# 03-POWER.net
KiCad netlist of a schematic drawn in Altium Designer
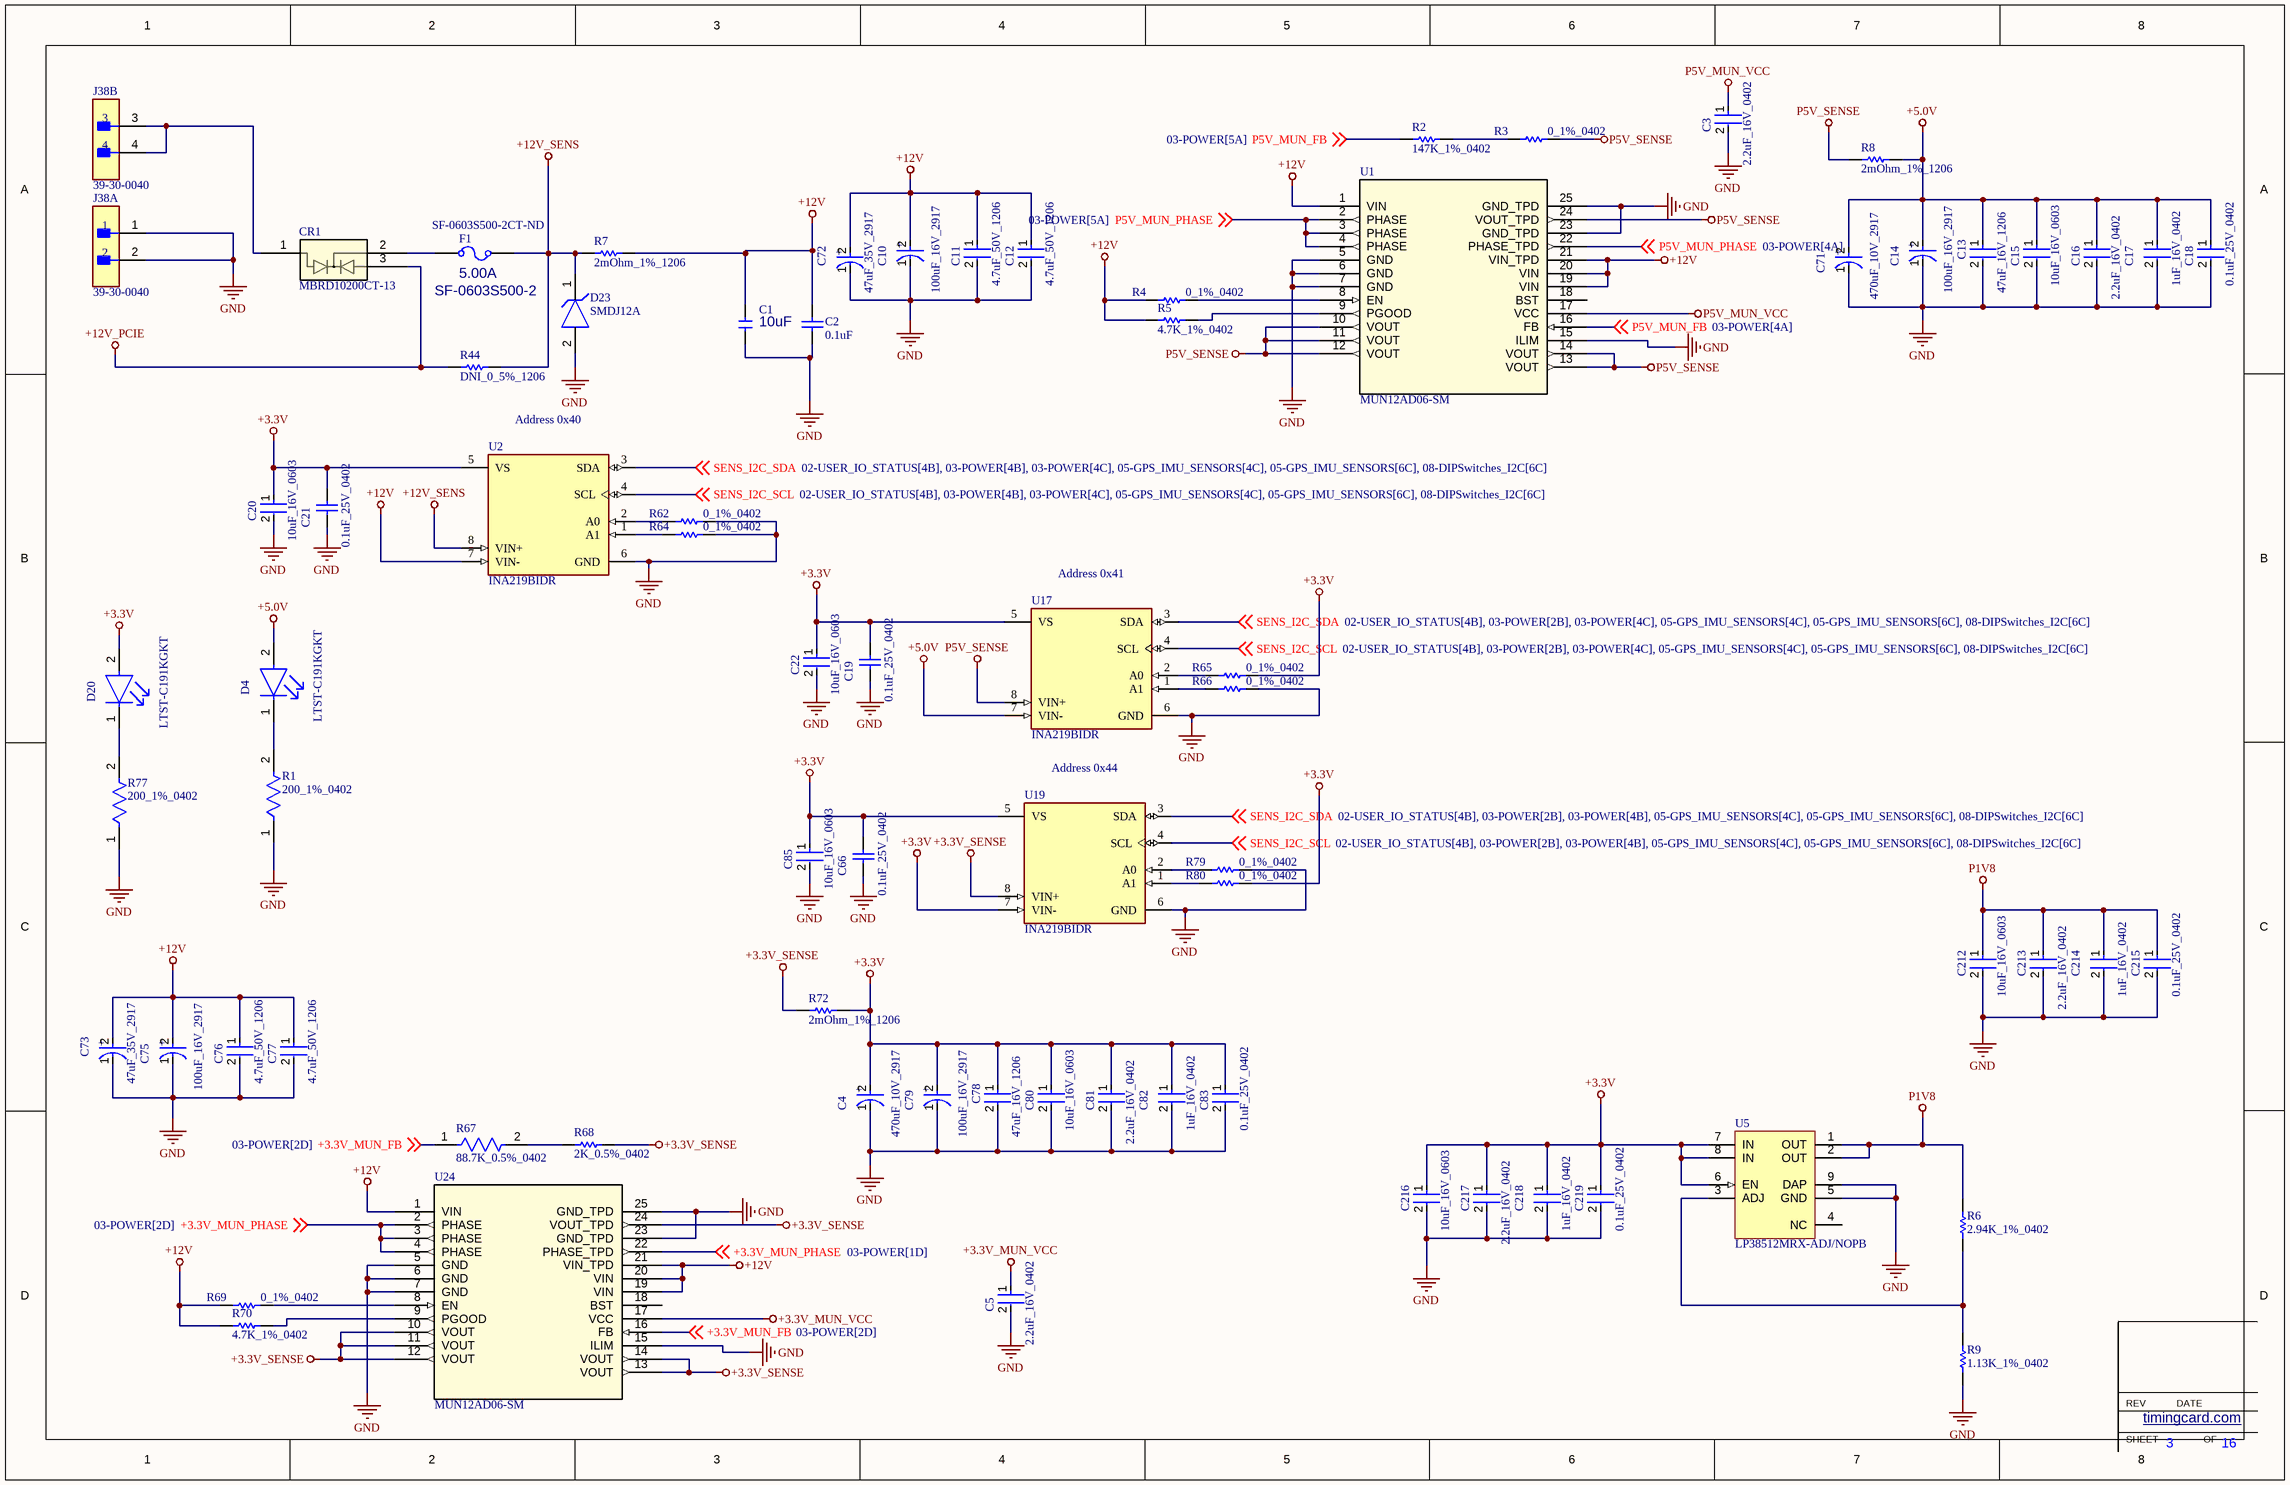
[diagram p0: 03-POWER.SchDoc]

(export (version "E")
  (design (tool "Eeschema 10.0.6"))
  (components
    (comp (ref "C1")
      (value "10uF")
      (footprint "CAPC2012X14N")
      (description "CAP, CER, 10.UF, 25V, 10%, X5R, 0805")
      (fields
        (field (name "MFG PART NUM") "TMK212BBJ106KG-T")
        (field (name "VALENTIUM PART NUM") "<VALENTIUM>")
      )
      (libsource (lib "Capacitors") (part "CAP_0805_10UF_25V"))
    )
    (comp (ref "C2")
      (value "0.1uF")
      (footprint "CAPC1608X87X45ML20T05")
      (description "C0603X104K5RACAUTO")
      (fields (field (name "MANUFACTURER") "Kemet"))
      (libsource (lib "Altium Content Vault") (part "CAP"))
    )
    (comp (ref "C3")
      (value "2.2uF_16V_0402")
      (footprint "FP-C1005-050-0_05-IPC_A")
      (description "Multilayer Ceramic Capacitors 2.2μF ±10% 16V X5R SMD 0402")
      (fields (field (name "TOLERANCE") "10%"))
      (libsource (lib "Altium Content Vault") (part "b4654b650e69147ec39a6b967a45e02"))
    )
    (comp (ref "C4")
      (value "470uF_10V_2917")
      (footprint "FP-TAJE-MFG")
      (description "470uF 10V  ±10% 500mΩ 2917  SMD Tantalum Capacitor")
      (fields (field (name "TOLERANCE") "10%") (field (name "VOLTAGE") "10V"))
      (libsource (lib "Altium Content Vault") (part "203bc49f2ac43e59fd269a8c329ed05"))
    )
    (comp (ref "C5")
      (value "2.2uF_16V_0402")
      (footprint "FP-C1005-050-0_05-IPC_A")
      (description "Multilayer Ceramic Capacitors 2.2μF ±10% 16V X5R SMD 0402")
      (fields (field (name "TOLERANCE") "10%"))
      (libsource (lib "Altium Content Vault") (part "b4654b650e69147ec39a6b967a45e02"))
    )
    (comp (ref "C10")
      (value "100uF_16V_2917")
      (footprint "FP-T495D107K016ATE125-MFG")
      (description "CAP TANT 100UF 10% 16V 2917")
      (fields (field (name "VOLTAGE") "16V") (field (name "TOLERANCE") "10%"))
      (libsource (lib "Altium Content Vault") (part "a00bbbee19879c290e62620ae7e47b1"))
    )
    (comp (ref "C11")
      (value "4.7uF_50V_1206")
      (footprint "FP-GRM31C-0_2-e0_3_0_8-IPC_C")
      (description "Chip Multilayer Ceramic Capacitors for General Purpose, 1206, 4.7uF, X7R, 15%, 10%, 50V")
      (fields (field (name "VOLTAGE") "50V") (field (name "TOLERANCE") "10%"))
      (libsource (lib "Altium Content Vault") (part "02cd4be3c70576c341d710602a673aa"))
    )
    (comp (ref "C12")
      (value "4.7uF_50V_1206")
      (footprint "FP-GRM31C-0_2-e0_3_0_8-IPC_C")
      (description "Chip Multilayer Ceramic Capacitors for General Purpose, 1206, 4.7uF, X7R, 15%, 10%, 50V")
      (fields (field (name "VOLTAGE") "50V") (field (name "TOLERANCE") "10%"))
      (libsource (lib "Altium Content Vault") (part "02cd4be3c70576c341d710602a673aa"))
    )
    (comp (ref "C13")
      (value "47uF_16V_1206")
      (footprint "FP-C3216-160-0_2-MFG")
      (description "Multilayer Ceramic Capacitors 47uF ±20% 16V X5R SMD 1206")
      (fields (field (name "TOLERANCE") "20%"))
      (libsource (lib "Altium Content Vault") (part "11868f565c42a9108669ba33697ecf6"))
    )
    (comp (ref "C14")
      (value "100uF_16V_2917")
      (footprint "FP-T495D107K016ATE125-MFG")
      (description "CAP TANT 100UF 10% 16V 2917")
      (fields (field (name "VOLTAGE") "16V") (field (name "TOLERANCE") "10%"))
      (libsource (lib "Altium Content Vault") (part "a00bbbee19879c290e62620ae7e47b1"))
    )
    (comp (ref "C15")
      (value "10uF_16V_0603")
      (footprint "FP-0603-L_1_6_0_2-W_0_8_0-MFG")
      (description "Multilayer Ceramic Capacitor 10uF 16V X5R 20% SMD 0603 T/R")
      (fields (field (name "TOLERANCE") "20%"))
      (libsource (lib "Altium Content Vault") (part "b4654b650e69147ec39a6b967a45e02"))
    )
    (comp (ref "C16")
      (value "2.2uF_16V_0402")
      (footprint "FP-C1005-050-0_05-IPC_A")
      (description "Multilayer Ceramic Capacitors 2.2μF ±10% 16V X5R SMD 0402")
      (fields (field (name "TOLERANCE") "10%"))
      (libsource (lib "Altium Content Vault") (part "b4654b650e69147ec39a6b967a45e02"))
    )
    (comp (ref "C17")
      (value "1uF_16V_0402")
      (footprint "FP-0402-L_1_0_0_05-W_0_5-IPC_A")
      (description "None")
      (fields (field (name "TOLERANCE") "10%"))
      (libsource (lib "Altium Content Vault") (part "b4654b650e69147ec39a6b967a45e02"))
    )
    (comp (ref "C18")
      (value "0.1uF_25V_0402")
      (footprint "FP-0402-L_1_0_1-W_0_5_0_1-IPC_C")
      (description "General Purpose Ceramic Capacitor, 0402, 100nF, 10%, X7R, 15%, 25V")
      (fields (field (name "VOLTAGE") "25V") (field (name "TOLERANCE") "10%"))
      (libsource (lib "Altium Content Vault") (part "b4654b650e69147ec39a6b967a45e02"))
    )
    (comp (ref "C19")
      (value "0.1uF_25V_0402")
      (footprint "CAPC1005X56X25NL10T15")
      (fields
        (field (name "PART NUMBER") "04023D104KAT2A")
        (field (name "MANUFACTURER") "AVX Interconnect / Elco")
      )
      (libsource (lib "Altium Content Vault") (part "CAP"))
    )
    (comp (ref "C20")
      (value "10uF_16V_0603")
      (footprint "FP-0603-L_1_6_0_2-W_0_8_0-MFG")
      (description "Multilayer Ceramic Capacitor 10uF 16V X5R 20% SMD 0603 T/R")
      (fields (field (name "TOLERANCE") "20%"))
      (libsource (lib "Altium Content Vault") (part "b4654b650e69147ec39a6b967a45e02"))
    )
    (comp (ref "C21")
      (value "0.1uF_25V_0402")
      (footprint "CAPC1005X56X25NL10T15")
      (fields
        (field (name "PART NUMBER") "04023D104KAT2A")
        (field (name "MANUFACTURER") "AVX Interconnect / Elco")
      )
      (libsource (lib "Altium Content Vault") (part "CAP"))
    )
    (comp (ref "C22")
      (value "10uF_16V_0603")
      (footprint "FP-0603-L_1_6_0_2-W_0_8_0-MFG")
      (description "Multilayer Ceramic Capacitor 10uF 16V X5R 20% SMD 0603 T/R")
      (fields (field (name "TOLERANCE") "20%"))
      (libsource (lib "Altium Content Vault") (part "b4654b650e69147ec39a6b967a45e02"))
    )
    (comp (ref "C66")
      (value "0.1uF_25V_0402")
      (footprint "CAPC1005X56X25NL10T15")
      (fields
        (field (name "PART NUMBER") "04023D104KAT2A")
        (field (name "MANUFACTURER") "AVX Interconnect / Elco")
      )
      (libsource (lib "Altium Content Vault") (part "CAP"))
    )
    (comp (ref "C71")
      (value "470uF_10V_2917")
      (footprint "FP-TAJE-MFG")
      (description "470uF 10V  ±10% 500mΩ 2917  SMD Tantalum Capacitor")
      (fields (field (name "TOLERANCE") "10%") (field (name "VOLTAGE") "10V"))
      (libsource (lib "Altium Content Vault") (part "203bc49f2ac43e59fd269a8c329ed05"))
    )
    (comp (ref "C72")
      (value "47uF_35V_2917")
      (footprint "FP-T521X476M035ATE030-MFG")
      (description "CAP TANT POLY 47UF 35V 2917")
      (fields (field (name "TOLERANCE") "20%"))
      (libsource (lib "Altium Content Vault") (part "a00bbbee19879c290e62620ae7e47b1"))
    )
    (comp (ref "C73")
      (value "47uF_35V_2917")
      (footprint "FP-T521X476M035ATE030-MFG")
      (description "CAP TANT POLY 47UF 35V 2917")
      (fields (field (name "TOLERANCE") "20%"))
      (libsource (lib "Altium Content Vault") (part "a00bbbee19879c290e62620ae7e47b1"))
    )
    (comp (ref "C75")
      (value "100uF_16V_2917")
      (footprint "FP-T495D107K016ATE125-MFG")
      (description "CAP TANT 100UF 10% 16V 2917")
      (fields (field (name "VOLTAGE") "16V") (field (name "TOLERANCE") "10%"))
      (libsource (lib "Altium Content Vault") (part "a00bbbee19879c290e62620ae7e47b1"))
    )
    (comp (ref "C76")
      (value "4.7uF_50V_1206")
      (footprint "FP-GRM31C-0_2-e0_3_0_8-IPC_C")
      (description "Chip Multilayer Ceramic Capacitors for General Purpose, 1206, 4.7uF, X7R, 15%, 10%, 50V")
      (fields (field (name "VOLTAGE") "50V") (field (name "TOLERANCE") "10%"))
      (libsource (lib "Altium Content Vault") (part "02cd4be3c70576c341d710602a673aa"))
    )
    (comp (ref "C77")
      (value "4.7uF_50V_1206")
      (footprint "FP-GRM31C-0_2-e0_3_0_8-IPC_C")
      (description "Chip Multilayer Ceramic Capacitors for General Purpose, 1206, 4.7uF, X7R, 15%, 10%, 50V")
      (fields (field (name "VOLTAGE") "50V") (field (name "TOLERANCE") "10%"))
      (libsource (lib "Altium Content Vault") (part "02cd4be3c70576c341d710602a673aa"))
    )
    (comp (ref "C78")
      (value "47uF_16V_1206")
      (footprint "FP-C3216-160-0_2-MFG")
      (description "Multilayer Ceramic Capacitors 47uF ±20% 16V X5R SMD 1206")
      (fields (field (name "TOLERANCE") "20%"))
      (libsource (lib "Altium Content Vault") (part "11868f565c42a9108669ba33697ecf6"))
    )
    (comp (ref "C79")
      (value "100uF_16V_2917")
      (footprint "FP-T495D107K016ATE125-MFG")
      (description "CAP TANT 100UF 10% 16V 2917")
      (fields (field (name "VOLTAGE") "16V") (field (name "TOLERANCE") "10%"))
      (libsource (lib "Altium Content Vault") (part "a00bbbee19879c290e62620ae7e47b1"))
    )
    (comp (ref "C80")
      (value "10uF_16V_0603")
      (footprint "FP-0603-L_1_6_0_2-W_0_8_0-MFG")
      (description "Multilayer Ceramic Capacitor 10uF 16V X5R 20% SMD 0603 T/R")
      (fields (field (name "TOLERANCE") "20%"))
      (libsource (lib "Altium Content Vault") (part "b4654b650e69147ec39a6b967a45e02"))
    )
    (comp (ref "C81")
      (value "2.2uF_16V_0402")
      (footprint "FP-C1005-050-0_05-IPC_A")
      (description "Multilayer Ceramic Capacitors 2.2μF ±10% 16V X5R SMD 0402")
      (fields (field (name "TOLERANCE") "10%"))
      (libsource (lib "Altium Content Vault") (part "b4654b650e69147ec39a6b967a45e02"))
    )
    (comp (ref "C82")
      (value "1uF_16V_0402")
      (footprint "FP-0402-L_1_0_0_05-W_0_5-IPC_A")
      (description "None")
      (fields (field (name "TOLERANCE") "10%"))
      (libsource (lib "Altium Content Vault") (part "b4654b650e69147ec39a6b967a45e02"))
    )
    (comp (ref "C83")
      (value "0.1uF_25V_0402")
      (footprint "FP-0402-L_1_0_1-W_0_5_0_1-IPC_C")
      (description "General Purpose Ceramic Capacitor, 0402, 100nF, 10%, X7R, 15%, 25V")
      (fields (field (name "VOLTAGE") "25V") (field (name "TOLERANCE") "10%"))
      (libsource (lib "Altium Content Vault") (part "b4654b650e69147ec39a6b967a45e02"))
    )
    (comp (ref "C85")
      (value "10uF_16V_0603")
      (footprint "FP-0603-L_1_6_0_2-W_0_8_0-MFG")
      (description "Multilayer Ceramic Capacitor 10uF 16V X5R 20% SMD 0603 T/R")
      (fields (field (name "TOLERANCE") "20%"))
      (libsource (lib "Altium Content Vault") (part "b4654b650e69147ec39a6b967a45e02"))
    )
    (comp (ref "C212")
      (value "10uF_16V_0603")
      (footprint "FP-0603-L_1_6_0_2-W_0_8_0-MFG")
      (description "Multilayer Ceramic Capacitor 10uF 16V X5R 20% SMD 0603 T/R")
      (fields (field (name "TOLERANCE") "20%"))
      (libsource (lib "Altium Content Vault") (part "b4654b650e69147ec39a6b967a45e02"))
    )
    (comp (ref "C213")
      (value "2.2uF_16V_0402")
      (footprint "FP-C1005-050-0_05-IPC_A")
      (description "Multilayer Ceramic Capacitors 2.2μF ±10% 16V X5R SMD 0402")
      (fields (field (name "TOLERANCE") "10%"))
      (libsource (lib "Altium Content Vault") (part "b4654b650e69147ec39a6b967a45e02"))
    )
    (comp (ref "C214")
      (value "1uF_16V_0402")
      (footprint "FP-0402-L_1_0_0_05-W_0_5-IPC_A")
      (description "None")
      (fields (field (name "TOLERANCE") "10%"))
      (libsource (lib "Altium Content Vault") (part "b4654b650e69147ec39a6b967a45e02"))
    )
    (comp (ref "C215")
      (value "0.1uF_25V_0402")
      (footprint "FP-0402-L_1_0_1-W_0_5_0_1-IPC_C")
      (description "General Purpose Ceramic Capacitor, 0402, 100nF, 10%, X7R, 15%, 25V")
      (fields (field (name "VOLTAGE") "25V") (field (name "TOLERANCE") "10%"))
      (libsource (lib "Altium Content Vault") (part "b4654b650e69147ec39a6b967a45e02"))
    )
    (comp (ref "C216")
      (value "10uF_16V_0603")
      (footprint "FP-0603-L_1_6_0_2-W_0_8_0-MFG")
      (description "Multilayer Ceramic Capacitor 10uF 16V X5R 20% SMD 0603 T/R")
      (fields (field (name "TOLERANCE") "20%"))
      (libsource (lib "Altium Content Vault") (part "b4654b650e69147ec39a6b967a45e02"))
    )
    (comp (ref "C217")
      (value "2.2uF_16V_0402")
      (footprint "FP-C1005-050-0_05-IPC_A")
      (description "Multilayer Ceramic Capacitors 2.2μF ±10% 16V X5R SMD 0402")
      (fields (field (name "TOLERANCE") "10%"))
      (libsource (lib "Altium Content Vault") (part "b4654b650e69147ec39a6b967a45e02"))
    )
    (comp (ref "C218")
      (value "1uF_16V_0402")
      (footprint "FP-0402-L_1_0_0_05-W_0_5-IPC_A")
      (description "None")
      (fields (field (name "TOLERANCE") "10%"))
      (libsource (lib "Altium Content Vault") (part "b4654b650e69147ec39a6b967a45e02"))
    )
    (comp (ref "C219")
      (value "0.1uF_25V_0402")
      (footprint "FP-0402-L_1_0_1-W_0_5_0_1-IPC_C")
      (description "General Purpose Ceramic Capacitor, 0402, 100nF, 10%, X7R, 15%, 25V")
      (fields (field (name "VOLTAGE") "25V") (field (name "TOLERANCE") "10%"))
      (libsource (lib "Altium Content Vault") (part "b4654b650e69147ec39a6b967a45e02"))
    )
    (comp (ref "CR1")
      (value "MBRD10200CT-13")
      (footprint "TO252(DPAK)_DIO")
      (description "No Description Available")
      (libsource (lib "MBRD10200CT-13") (part "MBRD10200CT-13"))
    )
    (comp (ref "D4")
      (value "LTST-C191KGKT")
      (footprint "FP-LTST-C191KGKT-MFG")
      (description "LED GREEN CLEAR SMD")
      (libsource (lib "Altium Content Vault") (part "8706943c75ba83719d021d2fdc84c58"))
    )
    (comp (ref "D20")
      (value "LTST-C191KGKT")
      (footprint "FP-LTST-C191KGKT-MFG")
      (description "LED GREEN CLEAR SMD")
      (libsource (lib "Altium Content Vault") (part "8706943c75ba83719d021d2fdc84c58"))
    )
    (comp (ref "D23")
      (value "SMDJ12A")
      (footprint "FP-DO-214AB_SMC_J-Bend-MFG")
      (description "TVS DIODE 12V 19.9V DO214AB")
      (libsource (lib "Altium Content Vault") (part "673ecd2ea4d7fb87b4005b0cb348b7d"))
    )
    (comp (ref "F1")
      (value "5.00A")
      (footprint "FUSM1608X60N")
      (description "FUSE SLOW 5.00A 32V M 0603")
      (fields
        (field (name "MFG PART NUM") "SF-0603S500-2")
        (field (name "VALENTIUM PART NUM") "<VALENTIUM>")
        (field (name "SUPPLIER PART NUMBER 1") "SF-0603S500-2CT-ND")
        (field (name "Comment") "FUSE_0603_5.00A")
      )
      (libsource (lib "Passives") (part "FUSE_0603_2.00A"))
    )
    (comp (ref "J38")
      (value "39-30-0040")
      (footprint "FP-39-30-0040-MFG")
      (description "CONN HEADER R/A 4POS 4.2MM")
      (fields
        (field (name "OCTOPART") "https://octopart.com/39-30-0040-molex-277428")
        (field (name "MANUFACTURER") "Molex")
      )
      (libsource (lib "Altium Content Vault") (part "ac72c5313ea981db199dbd0e8237b04"))
    )
    (comp (ref "R1")
      (value "200_1%_0402")
      (footprint "FP-ERJ2RK-IPC_A")
      (description "RES SMD 200 OHM 1% 1/10W 0402")
      (fields (field (name "TOLERANCE") "1%"))
      (libsource (lib "Altium Content Vault") (part "1029c3af85768c4190bb7ad29bc67b5"))
    )
    (comp (ref "R2")
      (value "147K_1%_0402")
      (footprint "RESC1005X40X25ML05T10")
      (fields (field (name "MANUFACTURER") "Yageo / Phycomp") (field (name "PART NUMBER") "RC0402FR-07147KL"))
      (libsource (lib "Altium Content Vault") (part "RES"))
    )
    (comp (ref "R3")
      (value "0_1%_0402")
      (footprint "RESC1005X40X25LL05T05")
      (description "Chip Resistor, 0 Ohm, 0.1 W, -55 to 155 degC, 0402 (1005 Metric), RoHS, Tape and Reel")
      (fields (field (name "MANUFACTURER") "Panasonic") (field (name "TOLERANCE") "5%"))
      (libsource (lib "Altium Content Vault") (part "RES-2"))
    )
    (comp (ref "R4")
      (value "0_1%_0402")
      (footprint "RESC1005X40X25LL05T05")
      (description "Chip Resistor, 0 Ohm, 0.1 W, -55 to 155 degC, 0402 (1005 Metric), RoHS, Tape and Reel")
      (fields (field (name "MANUFACTURER") "Panasonic") (field (name "TOLERANCE") "5%"))
      (libsource (lib "Altium Content Vault") (part "RES-2"))
    )
    (comp (ref "R5")
      (value "4.7K_1%_0402")
      (footprint "RESC1005X40X25NL10T10")
      (fields (field (name "MANUFACTURER") "Bourns") (field (name "PART NUMBER") "CR0402-FX-4701GLF"))
      (libsource (lib "Altium Content Vault") (part "RES"))
    )
    (comp (ref "R6")
      (value "2.94K_1%_0402")
      (footprint "RESC1005X40X25ML05T10")
      (fields (field (name "MANUFACTURER") "Yageo") (field (name "PART NUMBER") "RC0402FR-072K94L"))
      (libsource (lib "Altium Content Vault") (part "RES"))
    )
    (comp (ref "R7")
      (value "2mOhm_1%_1206")
      (footprint "RESC3216X89X64NL25T25")
      (fields (field (name "MANUFACTURER") "Vishay Dale") (field (name "PART NUMBER") "WSL12062L000FEA18"))
      (libsource (lib "Altium Content Vault") (part "RES"))
    )
    (comp (ref "R8")
      (value "2mOhm_1%_1206")
      (footprint "RESC3216X89X64NL25T25")
      (fields (field (name "MANUFACTURER") "Vishay Dale") (field (name "PART NUMBER") "WSL12062L000FEA18"))
      (libsource (lib "Altium Content Vault") (part "RES"))
    )
    (comp (ref "R9")
      (value "1.13K_1%_0402")
      (footprint "RESC1005X40X25NL05T05")
      (fields (field (name "MANUFACTURER") "Panasonic") (field (name "PART NUMBER") "ERJ-2RKF1131X"))
      (libsource (lib "Altium Content Vault") (part "RES"))
    )
    (comp (ref "R44")
      (value "DNI_0_5%_1206")
      (footprint "RESC3116X65X50ML20T20")
      (fields (field (name "PART NUMBER") "CRCW12060000Z0EAHP") (field (name "MANUFACTURER") "Vishay Dale"))
      (libsource (lib "Altium Content Vault") (part "RES"))
    )
    (comp (ref "R62")
      (value "0_1%_0402")
      (footprint "RESC1005X40X25LL05T05")
      (description "Chip Resistor, 0 Ohm, 0.1 W, -55 to 155 degC, 0402 (1005 Metric), RoHS, Tape and Reel")
      (fields (field (name "MANUFACTURER") "Panasonic") (field (name "TOLERANCE") "5%"))
      (libsource (lib "Altium Content Vault") (part "RES-2"))
    )
    (comp (ref "R64")
      (value "0_1%_0402")
      (footprint "RESC1005X40X25LL05T05")
      (description "Chip Resistor, 0 Ohm, 0.1 W, -55 to 155 degC, 0402 (1005 Metric), RoHS, Tape and Reel")
      (fields (field (name "MANUFACTURER") "Panasonic") (field (name "TOLERANCE") "5%"))
      (libsource (lib "Altium Content Vault") (part "RES-2"))
    )
    (comp (ref "R65")
      (value "0_1%_0402")
      (footprint "RESC1005X40X25LL05T05")
      (description "Chip Resistor, 0 Ohm, 0.1 W, -55 to 155 degC, 0402 (1005 Metric), RoHS, Tape and Reel")
      (fields (field (name "MANUFACTURER") "Panasonic") (field (name "TOLERANCE") "5%"))
      (libsource (lib "Altium Content Vault") (part "RES-2"))
    )
    (comp (ref "R66")
      (value "0_1%_0402")
      (footprint "RESC1005X40X25LL05T05")
      (description "Chip Resistor, 0 Ohm, 0.1 W, -55 to 155 degC, 0402 (1005 Metric), RoHS, Tape and Reel")
      (fields (field (name "MANUFACTURER") "Panasonic") (field (name "TOLERANCE") "5%"))
      (libsource (lib "Altium Content Vault") (part "RES-2"))
    )
    (comp (ref "R67")
      (value "88.7K_0.5%_0402")
      (footprint "FP-RT0402-MFG")
      (description "RES SMD 88.7K OHM 0.5% 1/16W")
      (fields
        (field (name "OCTOPART") "https://octopart.com/rt0402dre0788k7l-yageo-1439224")
        (field (name "MANUFACTURER") "Yageo")
      )
      (libsource (lib "Altium Content Vault") (part "1029c3af85768c4190bb7ad29bc67b5"))
    )
    (comp (ref "R68")
      (value "2K_0.5%_0402")
      (footprint "RESC1005X35X25LL10T10")
      (fields (field (name "PART NUMBER") "RT0402DRD072KL") (field (name "MANUFACTURER") "Yageo"))
      (libsource (lib "Altium Content Vault") (part "RES"))
    )
    (comp (ref "R69")
      (value "0_1%_0402")
      (footprint "RESC1005X40X25LL05T05")
      (description "Chip Resistor, 0 Ohm, 0.1 W, -55 to 155 degC, 0402 (1005 Metric), RoHS, Tape and Reel")
      (fields (field (name "MANUFACTURER") "Panasonic") (field (name "TOLERANCE") "5%"))
      (libsource (lib "Altium Content Vault") (part "RES-2"))
    )
    (comp (ref "R70")
      (value "4.7K_1%_0402")
      (footprint "RESC1005X40X25NL10T10")
      (fields (field (name "MANUFACTURER") "Bourns") (field (name "PART NUMBER") "CR0402-FX-4701GLF"))
      (libsource (lib "Altium Content Vault") (part "RES"))
    )
    (comp (ref "R72")
      (value "2mOhm_1%_1206")
      (footprint "RESC3216X89X64NL25T25")
      (fields (field (name "MANUFACTURER") "Vishay Dale") (field (name "PART NUMBER") "WSL12062L000FEA18"))
      (libsource (lib "Altium Content Vault") (part "RES"))
    )
    (comp (ref "R77")
      (value "200_1%_0402")
      (footprint "FP-ERJ2RK-IPC_A")
      (description "RES SMD 200 OHM 1% 1/10W 0402")
      (fields (field (name "TOLERANCE") "1%"))
      (libsource (lib "Altium Content Vault") (part "1029c3af85768c4190bb7ad29bc67b5"))
    )
    (comp (ref "R79")
      (value "0_1%_0402")
      (footprint "RESC1005X40X25LL05T05")
      (description "Chip Resistor, 0 Ohm, 0.1 W, -55 to 155 degC, 0402 (1005 Metric), RoHS, Tape and Reel")
      (fields (field (name "MANUFACTURER") "Panasonic") (field (name "TOLERANCE") "5%"))
      (libsource (lib "Altium Content Vault") (part "RES-2"))
    )
    (comp (ref "R80")
      (value "0_1%_0402")
      (footprint "RESC1005X40X25LL05T05")
      (description "Chip Resistor, 0 Ohm, 0.1 W, -55 to 155 degC, 0402 (1005 Metric), RoHS, Tape and Reel")
      (fields (field (name "MANUFACTURER") "Panasonic") (field (name "TOLERANCE") "5%"))
      (libsource (lib "Altium Content Vault") (part "RES-2"))
    )
    (comp (ref "U1")
      (value "MUN12AD06-SM")
      (footprint "MUN12AD06-SM_CYN")
      (description "No Description Available")
      (libsource (lib "MUN12AD06-SM") (part "MUN12AD06-SM"))
    )
    (comp (ref "U2")
      (value "INA219BIDR")
      (footprint "FP-D0008A-MFG")
      (description "IC MONITOR PWR/CURR BIDIR 8-SOIC")
      (libsource (lib "Altium Content Vault") (part "41cc1aee4cbc9fa2660a15773fa0e79"))
    )
    (comp (ref "U5")
      (value "LP38512MRX-ADJ/NOPB")
      (footprint "MRA08B_M")
      (description "1.5A Fast-Transient Response Adjustable Low-Dropout Linear Voltage Regulator, 8-pin PSOP, Pb-Free")
      (fields (field (name "MANUFACTURER") "National Semiconductor"))
      (libsource (lib "Altium Content Vault") (part "PM-REG-LP38512MR-IL9"))
    )
    (comp (ref "U17")
      (value "INA219BIDR")
      (footprint "FP-D0008A-MFG")
      (description "IC MONITOR PWR/CURR BIDIR 8-SOIC")
      (libsource (lib "Altium Content Vault") (part "41cc1aee4cbc9fa2660a15773fa0e79"))
    )
    (comp (ref "U19")
      (value "INA219BIDR")
      (footprint "FP-D0008A-MFG")
      (description "IC MONITOR PWR/CURR BIDIR 8-SOIC")
      (libsource (lib "Altium Content Vault") (part "41cc1aee4cbc9fa2660a15773fa0e79"))
    )
    (comp (ref "U24")
      (value "MUN12AD06-SM")
      (footprint "MUN12AD06-SM_CYN")
      (description "No Description Available")
      (libsource (lib "MUN12AD06-SM") (part "MUN12AD06-SM"))
    )
  )
  (nets
    (net (code "1") (name "+3.3V") (class "Default")
      (node (ref "C19") (pin "2") (pinfunction "2_2") (pintype "passive"))
      (node (ref "C20") (pin "1") (pinfunction "1_1") (pintype "passive"))
      (node (ref "C21") (pin "2") (pinfunction "2_2") (pintype "passive"))
      (node (ref "C216") (pin "1") (pinfunction "1_1") (pintype "passive"))
      (node (ref "C217") (pin "1") (pinfunction "1_1") (pintype "passive"))
      (node (ref "C218") (pin "1") (pinfunction "1_1") (pintype "passive"))
      (node (ref "C219") (pin "1") (pinfunction "1_1") (pintype "passive"))
      (node (ref "C22") (pin "1") (pinfunction "1_1") (pintype "passive"))
      (node (ref "C4") (pin "2") (pinfunction "A_2") (pintype "passive"))
      (node (ref "C66") (pin "2") (pinfunction "2_2") (pintype "passive"))
      (node (ref "C78") (pin "1") (pinfunction "1_1") (pintype "passive"))
      (node (ref "C79") (pin "2") (pinfunction "A_2") (pintype "passive"))
      (node (ref "C80") (pin "1") (pinfunction "1_1") (pintype "passive"))
      (node (ref "C81") (pin "1") (pinfunction "1_1") (pintype "passive"))
      (node (ref "C82") (pin "1") (pinfunction "1_1") (pintype "passive"))
      (node (ref "C83") (pin "1") (pinfunction "1_1") (pintype "passive"))
      (node (ref "C85") (pin "1") (pinfunction "1_1") (pintype "passive"))
      (node (ref "D20") (pin "2") (pinfunction "A_2") (pintype "passive"))
      (node (ref "R65") (pin "2") (pinfunction "2_2") (pintype "passive"))
      (node (ref "R72") (pin "2") (pinfunction "2_2") (pintype "passive"))
      (node (ref "R80") (pin "2") (pinfunction "2_2") (pintype "passive"))
      (node (ref "U17") (pin "5") (pinfunction "VS_5") (pintype "power_in"))
      (node (ref "U19") (pin "5") (pinfunction "VS_5") (pintype "power_in"))
      (node (ref "U19") (pin "7") (pinfunction "VIN-_7") (pintype "input"))
      (node (ref "U2") (pin "5") (pinfunction "VS_5") (pintype "power_in"))
      (node (ref "U5") (pin "6") (pinfunction "EN_6") (pintype "input"))
      (node (ref "U5") (pin "7") (pinfunction "IN_7") (pintype "power_in"))
      (node (ref "U5") (pin "8") (pinfunction "IN_8") (pintype "power_in"))
    )
    (net (code "2") (name "+3.3V_MUN_FB") (class "Default")
      (node (ref "R67") (pin "1") (pinfunction "1_1") (pintype "passive"))
      (node (ref "U24") (pin "16") (pinfunction "FB_16") (pintype "input"))
    )
    (net (code "3") (name "+3.3V_MUN_PHASE") (class "Default")
      (node (ref "U24") (pin "2") (pinfunction "PHASE_2") (pintype "output"))
      (node (ref "U24") (pin "22") (pinfunction "PHASE_TPD_22") (pintype "output"))
      (node (ref "U24") (pin "3") (pinfunction "PHASE_3") (pintype "output"))
      (node (ref "U24") (pin "4") (pinfunction "PHASE_4") (pintype "output"))
    )
    (net (code "4") (name "+3.3V_MUN_VCC") (class "Default")
      (node (ref "C5") (pin "1") (pinfunction "1_1") (pintype "passive"))
      (node (ref "U24") (pin "17") (pinfunction "VCC_17") (pintype "power_in"))
    )
    (net (code "5") (name "+3.3V_SENSE") (class "Default")
      (node (ref "R68") (pin "2") (pinfunction "2_2") (pintype "passive"))
      (node (ref "R72") (pin "1") (pinfunction "1_1") (pintype "passive"))
      (node (ref "U19") (pin "8") (pinfunction "VIN+_8") (pintype "input"))
      (node (ref "U24") (pin "10") (pinfunction "VOUT_10") (pintype "output"))
      (node (ref "U24") (pin "11") (pinfunction "VOUT_11") (pintype "output"))
      (node (ref "U24") (pin "12") (pinfunction "VOUT_12") (pintype "output"))
      (node (ref "U24") (pin "13") (pinfunction "VOUT_13") (pintype "output"))
      (node (ref "U24") (pin "14") (pinfunction "VOUT_14") (pintype "output"))
      (node (ref "U24") (pin "24") (pinfunction "VOUT_TPD_24") (pintype "output"))
    )
    (net (code "6") (name "+5.0V") (class "Default")
      (node (ref "C13") (pin "1") (pinfunction "1_1") (pintype "passive"))
      (node (ref "C14") (pin "2") (pinfunction "A_2") (pintype "passive"))
      (node (ref "C15") (pin "1") (pinfunction "1_1") (pintype "passive"))
      (node (ref "C16") (pin "1") (pinfunction "1_1") (pintype "passive"))
      (node (ref "C17") (pin "1") (pinfunction "1_1") (pintype "passive"))
      (node (ref "C18") (pin "1") (pinfunction "1_1") (pintype "passive"))
      (node (ref "C71") (pin "2") (pinfunction "A_2") (pintype "passive"))
      (node (ref "D4") (pin "2") (pinfunction "A_2") (pintype "passive"))
      (node (ref "R8") (pin "2") (pinfunction "2_2") (pintype "passive"))
      (node (ref "U17") (pin "7") (pinfunction "VIN-_7") (pintype "input"))
    )
    (net (code "7") (name "+12V") (class "Default")
      (node (ref "C1") (pin "1") (pinfunction "1_1") (pintype "passive"))
      (node (ref "C10") (pin "2") (pinfunction "A_2") (pintype "passive"))
      (node (ref "C11") (pin "1") (pinfunction "1_1") (pintype "passive"))
      (node (ref "C12") (pin "1") (pinfunction "1_1") (pintype "passive"))
      (node (ref "C2") (pin "2") (pinfunction "2_2") (pintype "passive"))
      (node (ref "C72") (pin "2") (pinfunction "A_2") (pintype "passive"))
      (node (ref "C73") (pin "2") (pinfunction "A_2") (pintype "passive"))
      (node (ref "C75") (pin "2") (pinfunction "A_2") (pintype "passive"))
      (node (ref "C76") (pin "1") (pinfunction "1_1") (pintype "passive"))
      (node (ref "C77") (pin "1") (pinfunction "1_1") (pintype "passive"))
      (node (ref "R4") (pin "1") (pinfunction "1_1") (pintype "passive"))
      (node (ref "R5") (pin "2") (pinfunction "2_2") (pintype "passive"))
      (node (ref "R69") (pin "1") (pinfunction "1_1") (pintype "passive"))
      (node (ref "R7") (pin "2") (pinfunction "2_2") (pintype "passive"))
      (node (ref "R70") (pin "2") (pinfunction "2_2") (pintype "passive"))
      (node (ref "U1") (pin "1") (pinfunction "VIN_1") (pintype "power_in"))
      (node (ref "U1") (pin "19") (pinfunction "VIN_19") (pintype "power_in"))
      (node (ref "U1") (pin "20") (pinfunction "VIN_20") (pintype "power_in"))
      (node (ref "U1") (pin "21") (pinfunction "VIN_TPD_21") (pintype "power_in"))
      (node (ref "U2") (pin "7") (pinfunction "VIN-_7") (pintype "input"))
      (node (ref "U24") (pin "1") (pinfunction "VIN_1") (pintype "power_in"))
      (node (ref "U24") (pin "19") (pinfunction "VIN_19") (pintype "power_in"))
      (node (ref "U24") (pin "20") (pinfunction "VIN_20") (pintype "power_in"))
      (node (ref "U24") (pin "21") (pinfunction "VIN_TPD_21") (pintype "power_in"))
    )
    (net (code "8") (name "+12V_PCIE") (class "Default")
      (node (ref "CR1") (pin "3") (pinfunction "3_3") (pintype "passive"))
      (node (ref "R44") (pin "1") (pinfunction "1_1") (pintype "passive"))
    )
    (net (code "9") (name "+12V_SENS") (class "Default")
      (node (ref "D23") (pin "1") (pinfunction "C_1") (pintype "passive"))
      (node (ref "F1") (pin "2") (pinfunction "2_2") (pintype "passive"))
      (node (ref "R44") (pin "2") (pinfunction "2_2") (pintype "passive"))
      (node (ref "R7") (pin "1") (pinfunction "1_1") (pintype "passive"))
      (node (ref "U2") (pin "8") (pinfunction "VIN+_8") (pintype "input"))
    )
    (net (code "10") (name "GND") (class "Default")
      (node (ref "C1") (pin "2") (pinfunction "2_2") (pintype "passive"))
      (node (ref "C10") (pin "1") (pinfunction "C_1") (pintype "passive"))
      (node (ref "C11") (pin "2") (pinfunction "2_2") (pintype "passive"))
      (node (ref "C12") (pin "2") (pinfunction "2_2") (pintype "passive"))
      (node (ref "C13") (pin "2") (pinfunction "2_2") (pintype "passive"))
      (node (ref "C14") (pin "1") (pinfunction "C_1") (pintype "passive"))
      (node (ref "C15") (pin "2") (pinfunction "2_2") (pintype "passive"))
      (node (ref "C16") (pin "2") (pinfunction "2_2") (pintype "passive"))
      (node (ref "C17") (pin "2") (pinfunction "2_2") (pintype "passive"))
      (node (ref "C18") (pin "2") (pinfunction "2_2") (pintype "passive"))
      (node (ref "C19") (pin "1") (pinfunction "1_1") (pintype "passive"))
      (node (ref "C2") (pin "1") (pinfunction "1_1") (pintype "passive"))
      (node (ref "C20") (pin "2") (pinfunction "2_2") (pintype "passive"))
      (node (ref "C21") (pin "1") (pinfunction "1_1") (pintype "passive"))
      (node (ref "C212") (pin "2") (pinfunction "2_2") (pintype "passive"))
      (node (ref "C213") (pin "2") (pinfunction "2_2") (pintype "passive"))
      (node (ref "C214") (pin "2") (pinfunction "2_2") (pintype "passive"))
      (node (ref "C215") (pin "2") (pinfunction "2_2") (pintype "passive"))
      (node (ref "C216") (pin "2") (pinfunction "2_2") (pintype "passive"))
      (node (ref "C217") (pin "2") (pinfunction "2_2") (pintype "passive"))
      (node (ref "C218") (pin "2") (pinfunction "2_2") (pintype "passive"))
      (node (ref "C219") (pin "2") (pinfunction "2_2") (pintype "passive"))
      (node (ref "C22") (pin "2") (pinfunction "2_2") (pintype "passive"))
      (node (ref "C3") (pin "2") (pinfunction "2_2") (pintype "passive"))
      (node (ref "C4") (pin "1") (pinfunction "C_1") (pintype "passive"))
      (node (ref "C5") (pin "2") (pinfunction "2_2") (pintype "passive"))
      (node (ref "C66") (pin "1") (pinfunction "1_1") (pintype "passive"))
      (node (ref "C71") (pin "1") (pinfunction "C_1") (pintype "passive"))
      (node (ref "C72") (pin "1") (pinfunction "C_1") (pintype "passive"))
      (node (ref "C73") (pin "1") (pinfunction "C_1") (pintype "passive"))
      (node (ref "C75") (pin "1") (pinfunction "C_1") (pintype "passive"))
      (node (ref "C76") (pin "2") (pinfunction "2_2") (pintype "passive"))
      (node (ref "C77") (pin "2") (pinfunction "2_2") (pintype "passive"))
      (node (ref "C78") (pin "2") (pinfunction "2_2") (pintype "passive"))
      (node (ref "C79") (pin "1") (pinfunction "C_1") (pintype "passive"))
      (node (ref "C80") (pin "2") (pinfunction "2_2") (pintype "passive"))
      (node (ref "C81") (pin "2") (pinfunction "2_2") (pintype "passive"))
      (node (ref "C82") (pin "2") (pinfunction "2_2") (pintype "passive"))
      (node (ref "C83") (pin "2") (pinfunction "2_2") (pintype "passive"))
      (node (ref "C85") (pin "2") (pinfunction "2_2") (pintype "passive"))
      (node (ref "D23") (pin "2") (pinfunction "A_2") (pintype "passive"))
      (node (ref "J38") (pin "1") (pinfunction "1_1") (pintype "passive"))
      (node (ref "J38") (pin "2") (pinfunction "2_2") (pintype "passive"))
      (node (ref "R1") (pin "1") (pinfunction "1_1") (pintype "passive"))
      (node (ref "R62") (pin "2") (pinfunction "2_2") (pintype "passive"))
      (node (ref "R64") (pin "2") (pinfunction "2_2") (pintype "passive"))
      (node (ref "R66") (pin "2") (pinfunction "2_2") (pintype "passive"))
      (node (ref "R77") (pin "1") (pinfunction "1_1") (pintype "passive"))
      (node (ref "R79") (pin "2") (pinfunction "2_2") (pintype "passive"))
      (node (ref "R9") (pin "1") (pinfunction "1_1") (pintype "passive"))
      (node (ref "U1") (pin "15") (pinfunction "ILIM_15") (pintype "passive"))
      (node (ref "U1") (pin "23") (pinfunction "GND_TPD_23") (pintype "power_in"))
      (node (ref "U1") (pin "25") (pinfunction "GND_TPD_25") (pintype "power_in"))
      (node (ref "U1") (pin "5") (pinfunction "GND_5") (pintype "power_in"))
      (node (ref "U1") (pin "6") (pinfunction "GND_6") (pintype "power_in"))
      (node (ref "U1") (pin "7") (pinfunction "GND_7") (pintype "power_in"))
      (node (ref "U17") (pin "6") (pinfunction "GND_6") (pintype "power_in"))
      (node (ref "U19") (pin "6") (pinfunction "GND_6") (pintype "power_in"))
      (node (ref "U2") (pin "6") (pinfunction "GND_6") (pintype "power_in"))
      (node (ref "U24") (pin "15") (pinfunction "ILIM_15") (pintype "passive"))
      (node (ref "U24") (pin "23") (pinfunction "GND_TPD_23") (pintype "power_in"))
      (node (ref "U24") (pin "25") (pinfunction "GND_TPD_25") (pintype "power_in"))
      (node (ref "U24") (pin "5") (pinfunction "GND_5") (pintype "power_in"))
      (node (ref "U24") (pin "6") (pinfunction "GND_6") (pintype "power_in"))
      (node (ref "U24") (pin "7") (pinfunction "GND_7") (pintype "power_in"))
      (node (ref "U5") (pin "5") (pinfunction "GND_5") (pintype "power_in"))
      (node (ref "U5") (pin "9") (pinfunction "DAP_9") (pintype "passive"))
    )
    (net (code "11") (name "Net-(CR1-Pad1)") (class "Default")
      (node (ref "CR1") (pin "1") (pinfunction "1_1") (pintype "passive"))
      (node (ref "J38") (pin "3") (pinfunction "3_3") (pintype "passive"))
      (node (ref "J38") (pin "4") (pinfunction "4_4") (pintype "passive"))
    )
    (net (code "12") (name "Net-(CR1-Pad2)") (class "Default")
      (node (ref "CR1") (pin "2") (pinfunction "2_2") (pintype "passive"))
      (node (ref "F1") (pin "1") (pinfunction "1_1") (pintype "passive"))
    )
    (net (code "13") (name "Net-(D4-C)") (class "Default")
      (node (ref "D4") (pin "1") (pinfunction "C_1") (pintype "passive"))
      (node (ref "R1") (pin "2") (pinfunction "2_2") (pintype "passive"))
    )
    (net (code "14") (name "Net-(D20-C)") (class "Default")
      (node (ref "D20") (pin "1") (pinfunction "C_1") (pintype "passive"))
      (node (ref "R77") (pin "2") (pinfunction "2_2") (pintype "passive"))
    )
    (net (code "15") (name "Net-(R2-Pad2)") (class "Default")
      (node (ref "R2") (pin "2") (pinfunction "2_2") (pintype "passive"))
      (node (ref "R3") (pin "1") (pinfunction "1_1") (pintype "passive"))
    )
    (net (code "16") (name "Net-(R67-Pad2)") (class "Default")
      (node (ref "R67") (pin "2") (pinfunction "2_2") (pintype "passive"))
      (node (ref "R68") (pin "1") (pinfunction "1_1") (pintype "passive"))
    )
    (net (code "17") (name "Net-(U1-EN)") (class "Default")
      (node (ref "R4") (pin "2") (pinfunction "2_2") (pintype "passive"))
      (node (ref "U1") (pin "8") (pinfunction "EN_8") (pintype "input"))
    )
    (net (code "18") (name "Net-(U1-PGOOD)") (class "Default")
      (node (ref "R5") (pin "1") (pinfunction "1_1") (pintype "passive"))
      (node (ref "U1") (pin "9") (pinfunction "PGOOD_9") (pintype "output"))
    )
    (net (code "19") (name "Net-(U2-A0)") (class "Default")
      (node (ref "R62") (pin "1") (pinfunction "1_1") (pintype "passive"))
      (node (ref "U2") (pin "2") (pinfunction "A0_2") (pintype "input"))
    )
    (net (code "20") (name "Net-(U2-A1)") (class "Default")
      (node (ref "R64") (pin "1") (pinfunction "1_1") (pintype "passive"))
      (node (ref "U2") (pin "1") (pinfunction "A1_1") (pintype "input"))
    )
    (net (code "21") (name "Net-(U5-ADJ)") (class "Default")
      (node (ref "R6") (pin "1") (pinfunction "1_1") (pintype "passive"))
      (node (ref "R9") (pin "2") (pinfunction "2_2") (pintype "passive"))
      (node (ref "U5") (pin "3") (pinfunction "ADJ_3") (pintype "passive"))
    )
    (net (code "22") (name "Net-(U17-A0)") (class "Default")
      (node (ref "R65") (pin "1") (pinfunction "1_1") (pintype "passive"))
      (node (ref "U17") (pin "2") (pinfunction "A0_2") (pintype "input"))
    )
    (net (code "23") (name "Net-(U17-A1)") (class "Default")
      (node (ref "R66") (pin "1") (pinfunction "1_1") (pintype "passive"))
      (node (ref "U17") (pin "1") (pinfunction "A1_1") (pintype "input"))
    )
    (net (code "24") (name "Net-(U19-A0)") (class "Default")
      (node (ref "R79") (pin "1") (pinfunction "1_1") (pintype "passive"))
      (node (ref "U19") (pin "2") (pinfunction "A0_2") (pintype "input"))
    )
    (net (code "25") (name "Net-(U19-A1)") (class "Default")
      (node (ref "R80") (pin "1") (pinfunction "1_1") (pintype "passive"))
      (node (ref "U19") (pin "1") (pinfunction "A1_1") (pintype "input"))
    )
    (net (code "26") (name "Net-(U24-EN)") (class "Default")
      (node (ref "R69") (pin "2") (pinfunction "2_2") (pintype "passive"))
      (node (ref "U24") (pin "8") (pinfunction "EN_8") (pintype "input"))
    )
    (net (code "27") (name "Net-(U24-PGOOD)") (class "Default")
      (node (ref "R70") (pin "1") (pinfunction "1_1") (pintype "passive"))
      (node (ref "U24") (pin "9") (pinfunction "PGOOD_9") (pintype "output"))
    )
    (net (code "28") (name "P1V8") (class "Default")
      (node (ref "C212") (pin "1") (pinfunction "1_1") (pintype "passive"))
      (node (ref "C213") (pin "1") (pinfunction "1_1") (pintype "passive"))
      (node (ref "C214") (pin "1") (pinfunction "1_1") (pintype "passive"))
      (node (ref "C215") (pin "1") (pinfunction "1_1") (pintype "passive"))
      (node (ref "R6") (pin "2") (pinfunction "2_2") (pintype "passive"))
      (node (ref "U5") (pin "1") (pinfunction "OUT_1") (pintype "power_in"))
      (node (ref "U5") (pin "2") (pinfunction "OUT_2") (pintype "power_in"))
    )
    (net (code "29") (name "P5V_MUN_FB") (class "Default")
      (node (ref "R2") (pin "1") (pinfunction "1_1") (pintype "passive"))
      (node (ref "U1") (pin "16") (pinfunction "FB_16") (pintype "input"))
    )
    (net (code "30") (name "P5V_MUN_PHASE") (class "Default")
      (node (ref "U1") (pin "2") (pinfunction "PHASE_2") (pintype "output"))
      (node (ref "U1") (pin "22") (pinfunction "PHASE_TPD_22") (pintype "output"))
      (node (ref "U1") (pin "3") (pinfunction "PHASE_3") (pintype "output"))
      (node (ref "U1") (pin "4") (pinfunction "PHASE_4") (pintype "output"))
    )
    (net (code "31") (name "P5V_MUN_VCC") (class "Default")
      (node (ref "C3") (pin "1") (pinfunction "1_1") (pintype "passive"))
      (node (ref "U1") (pin "17") (pinfunction "VCC_17") (pintype "power_in"))
    )
    (net (code "32") (name "P5V_SENSE") (class "Default")
      (node (ref "R3") (pin "2") (pinfunction "2_2") (pintype "passive"))
      (node (ref "R8") (pin "1") (pinfunction "1_1") (pintype "passive"))
      (node (ref "U1") (pin "10") (pinfunction "VOUT_10") (pintype "output"))
      (node (ref "U1") (pin "11") (pinfunction "VOUT_11") (pintype "output"))
      (node (ref "U1") (pin "12") (pinfunction "VOUT_12") (pintype "output"))
      (node (ref "U1") (pin "13") (pinfunction "VOUT_13") (pintype "output"))
      (node (ref "U1") (pin "14") (pinfunction "VOUT_14") (pintype "output"))
      (node (ref "U1") (pin "24") (pinfunction "VOUT_TPD_24") (pintype "output"))
      (node (ref "U17") (pin "8") (pinfunction "VIN+_8") (pintype "input"))
    )
    (net (code "33") (name "SENS_I2C_SCL") (class "Default")
      (node (ref "U17") (pin "4") (pinfunction "SCL_4") (pintype "bidirectional"))
      (node (ref "U19") (pin "4") (pinfunction "SCL_4") (pintype "bidirectional"))
      (node (ref "U2") (pin "4") (pinfunction "SCL_4") (pintype "bidirectional"))
    )
    (net (code "34") (name "SENS_I2C_SDA") (class "Default")
      (node (ref "U17") (pin "3") (pinfunction "SDA_3") (pintype "bidirectional"))
      (node (ref "U19") (pin "3") (pinfunction "SDA_3") (pintype "bidirectional"))
      (node (ref "U2") (pin "3") (pinfunction "SDA_3") (pintype "bidirectional"))
    )
    (net (code "35") (name "unconnected-(U1-BST-Pad18)") (class "Default")
      (node (ref "U1") (pin "18") (pinfunction "BST_18") (pintype "power_in"))
    )
    (net (code "36") (name "unconnected-(U5-NC-Pad4)") (class "Default")
      (node (ref "U5") (pin "4") (pinfunction "NC_4") (pintype "passive"))
    )
    (net (code "37") (name "unconnected-(U24-BST-Pad18)") (class "Default")
      (node (ref "U24") (pin "18") (pinfunction "BST_18") (pintype "power_in"))
    )
  )
)
